# cp2104.net
KiCad netlist of a schematic drawn in EAGLE
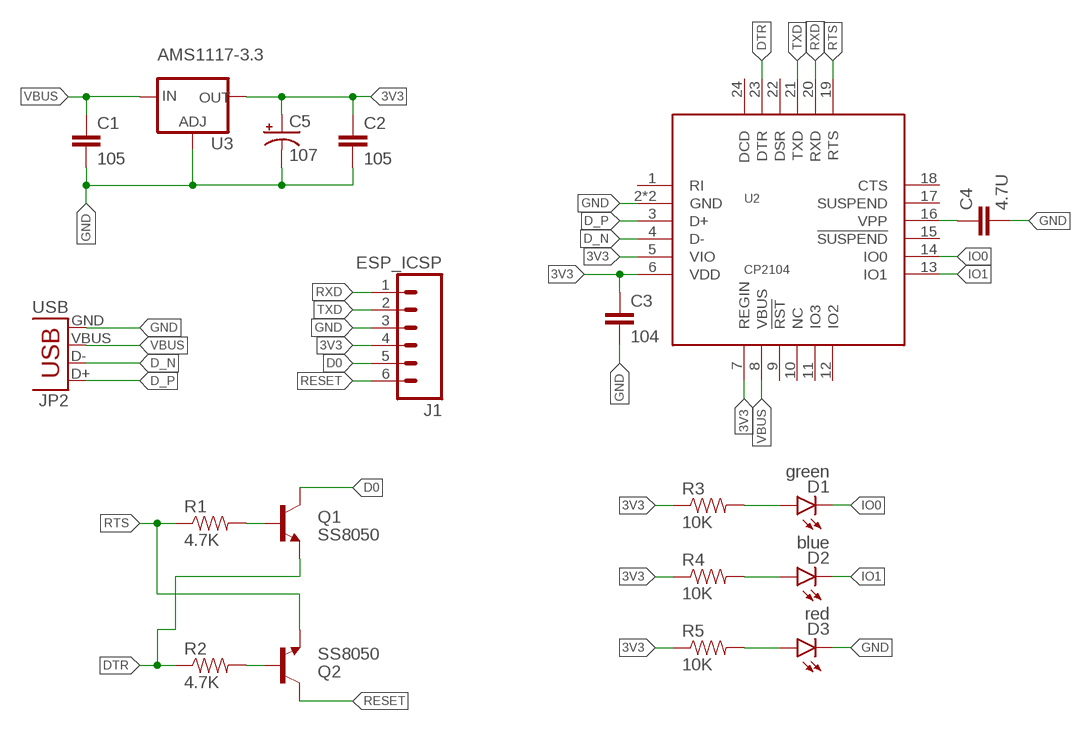
[diagram p0: schematic, sheet 1]

(export (version "E")
  (design (tool "Eeschema 10.0.6"))
  (components
    (comp (ref "C1")
      (value "105")
      (footprint "eagle-import:0603-CAP")
      (libsource (lib "eagle-import") (part "CAP0603-CAP"))
    )
    (comp (ref "C2")
      (value "105")
      (footprint "eagle-import:0603-CAP")
      (libsource (lib "eagle-import") (part "CAP0603-CAP"))
    )
    (comp (ref "C3")
      (value "104")
      (footprint "eagle-import:0603-CAP")
      (libsource (lib "eagle-import") (part "CAP0603-CAP"))
    )
    (comp (ref "C4")
      (value "4.7U")
      (footprint "eagle-import:0603-CAP")
      (libsource (lib "eagle-import") (part "CAP0603-CAP"))
    )
    (comp (ref "C5")
      (value "107")
      (footprint "eagle-import:EIA3528")
      (libsource (lib "eagle-import") (part "CAP_POL3528"))
    )
    (comp (ref "D1")
      (value "green")
      (footprint "eagle-import:LED-0603-SEEED")
      (libsource (lib "eagle-import") (part "LED-SEEED-0603"))
    )
    (comp (ref "D2")
      (value "blue")
      (footprint "eagle-import:LED-0603-SEEED")
      (libsource (lib "eagle-import") (part "LED-SEEED-0603"))
    )
    (comp (ref "D3")
      (value "red")
      (footprint "eagle-import:LED-0603-SEEED")
      (libsource (lib "eagle-import") (part "LED-SEEED-0603"))
    )
    (comp (ref "J1")
      (value "ESP_ICSP")
      (footprint "eagle-import:1X06_NO_SILK")
      (libsource (lib "eagle-import") (part "M06NO_SILK_FEMALE_PTH"))
    )
    (comp (ref "JP2")
      (value "USB")
      (footprint "eagle-import:MICROUSB-U-F-M5DD-Y-1")
      (libsource (lib "eagle-import") (part "USB"))
    )
    (comp (ref "Q1")
      (value "SS8050")
      (footprint "eagle-import:SOT23-3-JLC")
      (libsource (lib "eagle-import") (part "TRANSISTOR_NPN-JLC-SMT"))
    )
    (comp (ref "Q2")
      (value "SS8050")
      (footprint "eagle-import:SOT23-3-JLC")
      (libsource (lib "eagle-import") (part "TRANSISTOR_NPN-JLC-SMT"))
    )
    (comp (ref "R1")
      (value "4.7K")
      (footprint "eagle-import:0603-RES")
      (libsource (lib "eagle-import") (part "RESISTOR0603-RES"))
    )
    (comp (ref "R2")
      (value "4.7K")
      (footprint "eagle-import:0603-RES")
      (libsource (lib "eagle-import") (part "RESISTOR0603-RES"))
    )
    (comp (ref "R3")
      (value "10K")
      (footprint "eagle-import:0603-RES")
      (libsource (lib "eagle-import") (part "RESISTOR0603-RES"))
    )
    (comp (ref "R4")
      (value "10K")
      (footprint "eagle-import:0603-RES")
      (libsource (lib "eagle-import") (part "RESISTOR0603-RES"))
    )
    (comp (ref "R5")
      (value "10K")
      (footprint "eagle-import:0603-RES")
      (libsource (lib "eagle-import") (part "RESISTOR0603-RES"))
    )
    (comp (ref "U2")
      (value "CP2104")
      (footprint "eagle-import:QFN24")
      (libsource (lib "eagle-import") (part "CP2104"))
    )
    (comp (ref "U3")
      (value "AMS1117-3.3")
      (footprint "eagle-import:SOT223")
      (libsource (lib "eagle-import") (part "AMS1117SOT223"))
    )
  )
  (nets
    (net (code "1") (name "3V3") (class "Default")
      (node (ref "C2") (pin "1") (pinfunction "1_1") (pintype "passive"))
      (node (ref "C3") (pin "1") (pinfunction "1_1") (pintype "passive"))
      (node (ref "C5") (pin "A") (pinfunction "+_A") (pintype "passive"))
      (node (ref "J1") (pin "4") (pinfunction "4_4") (pintype "passive"))
      (node (ref "R3") (pin "1") (pinfunction "1_1") (pintype "passive"))
      (node (ref "R4") (pin "1") (pinfunction "1_1") (pintype "passive"))
      (node (ref "R5") (pin "1") (pinfunction "1_1") (pintype "passive"))
      (node (ref "U2") (pin "5") (pinfunction "VIO_5") (pintype "bidirectional"))
      (node (ref "U2") (pin "6") (pinfunction "VDD_6") (pintype "bidirectional"))
      (node (ref "U2") (pin "7") (pinfunction "REGIN_7") (pintype "bidirectional"))
      (node (ref "U3") (pin "2") (pinfunction "OUT_2") (pintype "output"))
      (node (ref "U3") (pin "4") (pinfunction "OUT_4") (pintype "output"))
    )
    (net (code "2") (name "D0") (class "Default")
      (node (ref "J1") (pin "5") (pinfunction "5_5") (pintype "passive"))
      (node (ref "Q1") (pin "3") (pinfunction "C_3") (pintype "passive"))
    )
    (net (code "3") (name "DTR") (class "Default")
      (node (ref "Q1") (pin "2") (pinfunction "E_2") (pintype "passive"))
      (node (ref "R2") (pin "1") (pinfunction "1_1") (pintype "passive"))
      (node (ref "U2") (pin "23") (pinfunction "DTR_23") (pintype "bidirectional"))
    )
    (net (code "4") (name "D_N") (class "Default")
      (node (ref "JP2") (pin "D-") (pinfunction "D-_D-") (pintype "bidirectional"))
      (node (ref "U2") (pin "4") (pinfunction "D-_4") (pintype "bidirectional"))
    )
    (net (code "5") (name "D_P") (class "Default")
      (node (ref "JP2") (pin "D+") (pinfunction "D+_D+") (pintype "bidirectional"))
      (node (ref "U2") (pin "3") (pinfunction "D+_3") (pintype "bidirectional"))
    )
    (net (code "6") (name "GND") (class "Default")
      (node (ref "C1") (pin "2") (pinfunction "2_2") (pintype "passive"))
      (node (ref "C2") (pin "2") (pinfunction "2_2") (pintype "passive"))
      (node (ref "C3") (pin "2") (pinfunction "2_2") (pintype "passive"))
      (node (ref "C4") (pin "2") (pinfunction "2_2") (pintype "passive"))
      (node (ref "C5") (pin "C") (pinfunction "-_C") (pintype "passive"))
      (node (ref "D3") (pin "-") (pinfunction "C_-") (pintype "passive"))
      (node (ref "J1") (pin "3") (pinfunction "3_3") (pintype "passive"))
      (node (ref "JP2") (pin "GND") (pinfunction "GND_GND") (pintype "bidirectional"))
      (node (ref "U2") (pin "2") (pinfunction "GND_2") (pintype "bidirectional"))
      (node (ref "U2") (pin "25") (pinfunction "GND_25") (pintype "bidirectional"))
      (node (ref "U3") (pin "1") (pinfunction "ADJ_1") (pintype "input"))
    )
    (net (code "7") (name "IO0") (class "Default")
      (node (ref "D1") (pin "-") (pinfunction "C_-") (pintype "passive"))
      (node (ref "U2") (pin "14") (pinfunction "IO0_14") (pintype "bidirectional"))
    )
    (net (code "8") (name "IO1") (class "Default")
      (node (ref "D2") (pin "-") (pinfunction "C_-") (pintype "passive"))
      (node (ref "U2") (pin "13") (pinfunction "IO1_13") (pintype "bidirectional"))
    )
    (net (code "9") (name "Net-(D1-A)") (class "Default")
      (node (ref "D1") (pin "+") (pinfunction "A_+") (pintype "passive"))
      (node (ref "R3") (pin "2") (pinfunction "2_2") (pintype "passive"))
    )
    (net (code "10") (name "Net-(D2-A)") (class "Default")
      (node (ref "D2") (pin "+") (pinfunction "A_+") (pintype "passive"))
      (node (ref "R4") (pin "2") (pinfunction "2_2") (pintype "passive"))
    )
    (net (code "11") (name "Net-(D3-A)") (class "Default")
      (node (ref "D3") (pin "+") (pinfunction "A_+") (pintype "passive"))
      (node (ref "R5") (pin "2") (pinfunction "2_2") (pintype "passive"))
    )
    (net (code "12") (name "Net-(Q1-B)") (class "Default")
      (node (ref "Q1") (pin "1") (pinfunction "B_1") (pintype "passive"))
      (node (ref "R1") (pin "2") (pinfunction "2_2") (pintype "passive"))
    )
    (net (code "13") (name "Net-(Q2-B)") (class "Default")
      (node (ref "Q2") (pin "1") (pinfunction "B_1") (pintype "passive"))
      (node (ref "R2") (pin "2") (pinfunction "2_2") (pintype "passive"))
    )
    (net (code "14") (name "Net-(U2-VPP)") (class "Default")
      (node (ref "C4") (pin "1") (pinfunction "1_1") (pintype "passive"))
      (node (ref "U2") (pin "16") (pinfunction "VPP_16") (pintype "bidirectional"))
    )
    (net (code "15") (name "RESET") (class "Default")
      (node (ref "J1") (pin "6") (pinfunction "6_6") (pintype "passive"))
      (node (ref "Q2") (pin "3") (pinfunction "C_3") (pintype "passive"))
    )
    (net (code "16") (name "RTS") (class "Default")
      (node (ref "Q2") (pin "2") (pinfunction "E_2") (pintype "passive"))
      (node (ref "R1") (pin "1") (pinfunction "1_1") (pintype "passive"))
      (node (ref "U2") (pin "19") (pinfunction "RTS_19") (pintype "bidirectional"))
    )
    (net (code "17") (name "RXD") (class "Default")
      (node (ref "J1") (pin "1") (pinfunction "1_1") (pintype "passive"))
      (node (ref "U2") (pin "20") (pinfunction "RXD_20") (pintype "bidirectional"))
    )
    (net (code "18") (name "TXD") (class "Default")
      (node (ref "J1") (pin "2") (pinfunction "2_2") (pintype "passive"))
      (node (ref "U2") (pin "21") (pinfunction "TXD_21") (pintype "bidirectional"))
    )
    (net (code "19") (name "VBUS") (class "Default")
      (node (ref "C1") (pin "1") (pinfunction "1_1") (pintype "passive"))
      (node (ref "JP2") (pin "VBUS") (pinfunction "VBUS_VBUS") (pintype "bidirectional"))
      (node (ref "U2") (pin "8") (pinfunction "VBUS_8") (pintype "bidirectional"))
      (node (ref "U3") (pin "3") (pinfunction "IN_3") (pintype "input"))
    )
    (net (code "20") (name "unconnected-(U2-CTS-Pad18)") (class "Default")
      (node (ref "U2") (pin "18") (pinfunction "CTS_18") (pintype "bidirectional"))
    )
    (net (code "21") (name "unconnected-(U2-DCD-Pad24)") (class "Default")
      (node (ref "U2") (pin "24") (pinfunction "DCD_24") (pintype "bidirectional"))
    )
    (net (code "22") (name "unconnected-(U2-DSR-Pad22)") (class "Default")
      (node (ref "U2") (pin "22") (pinfunction "DSR_22") (pintype "bidirectional"))
    )
    (net (code "23") (name "unconnected-(U2-IO2-Pad12)") (class "Default")
      (node (ref "U2") (pin "12") (pinfunction "IO2_12") (pintype "bidirectional"))
    )
    (net (code "24") (name "unconnected-(U2-IO3-Pad11)") (class "Default")
      (node (ref "U2") (pin "11") (pinfunction "IO3_11") (pintype "bidirectional"))
    )
    (net (code "25") (name "unconnected-(U2-NC-Pad10)") (class "Default")
      (node (ref "U2") (pin "10") (pinfunction "NC_10") (pintype "bidirectional"))
    )
    (net (code "26") (name "unconnected-(U2-RI-Pad1)") (class "Default")
      (node (ref "U2") (pin "1") (pinfunction "RI_1") (pintype "bidirectional"))
    )
    (net (code "27") (name "unconnected-(U2-SUSPEND-Pad17)") (class "Default")
      (node (ref "U2") (pin "17") (pinfunction "SUSPEND_17") (pintype "bidirectional"))
    )
    (net (code "28") (name "unconnected-(U2-~{RST}-Pad9)") (class "Default")
      (node (ref "U2") (pin "9") (pinfunction "~{RST}_9") (pintype "bidirectional"))
    )
    (net (code "29") (name "unconnected-(U2-~{SUSPEND}-Pad15)") (class "Default")
      (node (ref "U2") (pin "15") (pinfunction "~{SUSPEND}_15") (pintype "bidirectional"))
    )
  )
)
